# SP26_Magnetometer2_Polarization_Circuit_.net
KiCad netlist of a schematic drawn in Altium Designer
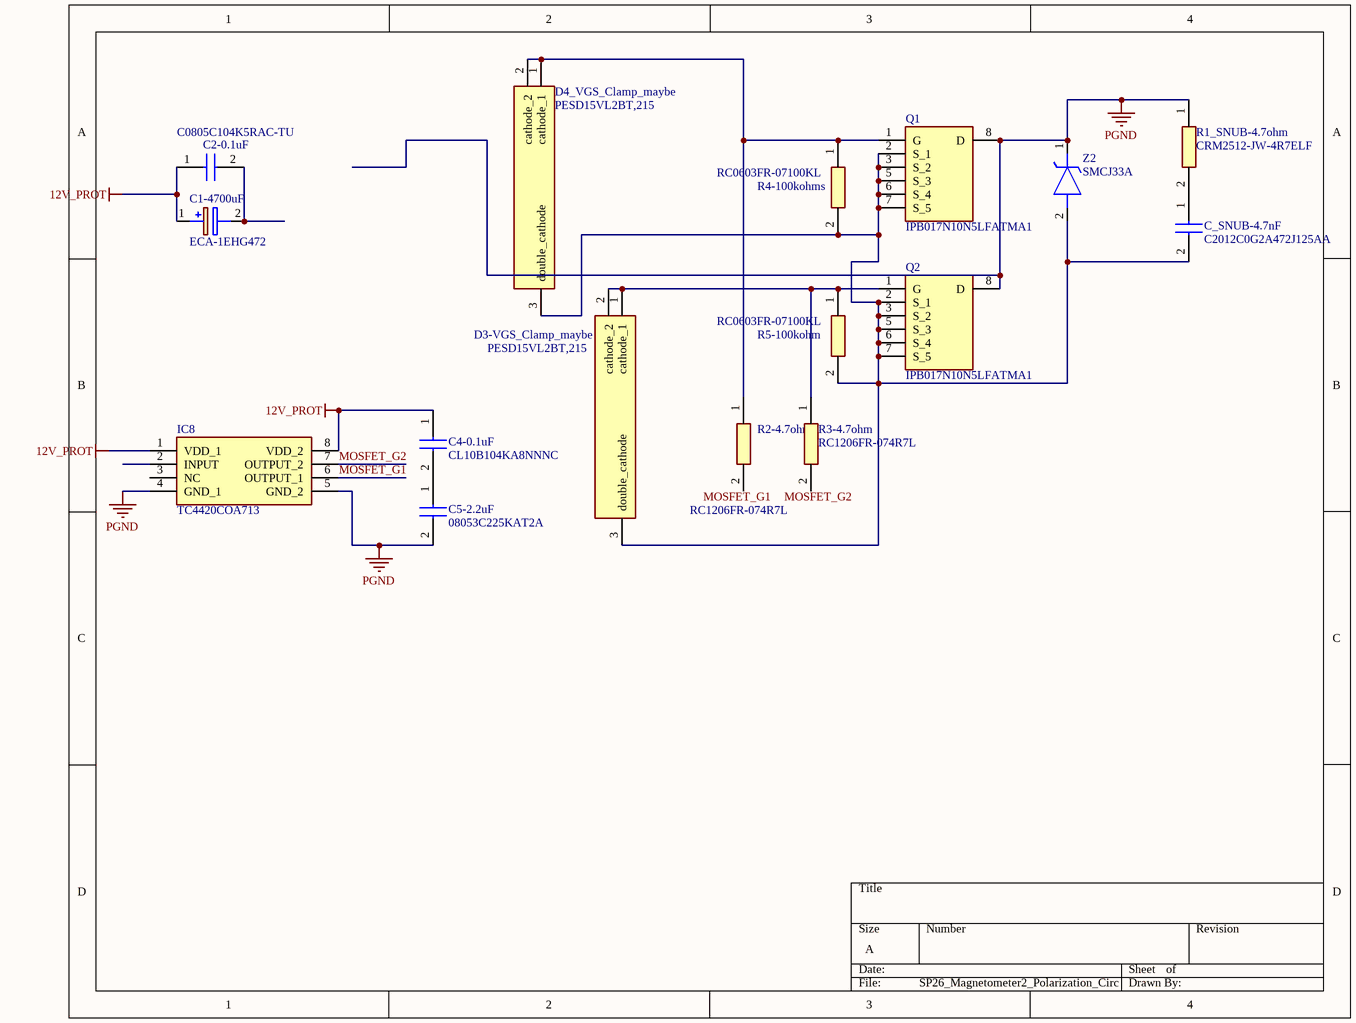
[diagram p0: SP26_Magnetometer2_Polarization_Circuit_Mason_Lebens.SchDoc]

(export (version "E")
  (design (tool "Eeschema 10.0.6"))
  (components
    (comp (ref "C1-4700uF")
      (value "ECA-1EHG472")
      (footprint "SamacSys:CAPPRD750W80D800H3150")
      (description "Capacitor Polarised")
      (fields (field (name "MOUSER PART NUMBER") "667-ECA-1EHG472"))
      (libsource (lib "*") (part "ECA-1EHG472"))
    )
    (comp (ref "C2-0.1uF")
      (value "C0805C104K5RAC-TU")
      (footprint "SamacSys:CAPC2012X88N")
      (description "Capacitor")
      (libsource (lib "*") (part "C0805C104K5RAC-TU"))
    )
    (comp (ref "C4-0.1uF")
      (value "CL10B104KA8NNNC")
      (footprint "SamacSys:CAPC1608X90N")
      (description "Capacitor")
      (fields (field (name "MOUSER PART NUMBER") "187-CL10B104KA8NNNC"))
      (libsource (lib "*") (part "CL10B104KA8NNNC"))
    )
    (comp (ref "C5-2.2uF")
      (value "08053C225KAT2A")
      (footprint "SamacSys:CAPC2012X152N")
      (description "Capacitor")
      (fields (field (name "MOUSER PART NUMBER") "581-08053C225K"))
      (libsource (lib "*") (part "08053C225KAT2A"))
    )
    (comp (ref "C_SNUB-4.7nF")
      (value "C2012C0G2A472J125AA")
      (footprint "SamacSys:CAPC2012X145N")
      (description "Capacitor")
      (fields (field (name "MOUSER PART NUMBER") "810-C2012C0G2A472J"))
      (libsource (lib "*") (part "C2012C0G2A472J125AA"))
    )
    (comp (ref "D3-VGS_Clamp_maybe")
      (value "PESD15VL2BT,215")
      (footprint "SamacSys:SOT95P230X110-3N")
      (description "Diode")
      (fields (field (name "MOUSER PART NUMBER") "771-PESD15VL2BT-T/R"))
      (libsource (lib "*") (part "PESD15VL2BT,215"))
    )
    (comp (ref "D4_VGS_Clamp_maybe")
      (value "PESD15VL2BT,215")
      (footprint "SamacSys:SOT95P230X110-3N")
      (description "Diode")
      (fields (field (name "MOUSER PART NUMBER") "771-PESD15VL2BT-T/R"))
      (libsource (lib "*") (part "PESD15VL2BT,215"))
    )
    (comp (ref "IC8")
      (value "TC4420COA713")
      (footprint "SamacSys:SOIC127P600X175-8N")
      (description "Integrated Circuit")
      (fields (field (name "MOUSER PART NUMBER") "579-TC4420COA713"))
      (libsource (lib "*") (part "TC4420COA713"))
    )
    (comp (ref "Q1")
      (value "IPB017N10N5LFATMA1")
      (footprint "SamacSys:PG-TO263-7-3_3")
      (description "MOSFET (N-Channel)")
      (fields (field (name "MOUSER PART NUMBER") "726-IPB017N10N5LFATM"))
      (libsource (lib "*") (part "IPB017N10N5LFATMA1"))
    )
    (comp (ref "Q2")
      (value "IPB017N10N5LFATMA1")
      (footprint "SamacSys:PG-TO263-7-3_3")
      (description "MOSFET (N-Channel)")
      (fields (field (name "MOUSER PART NUMBER") "726-IPB017N10N5LFATM"))
      (libsource (lib "*") (part "IPB017N10N5LFATMA1"))
    )
    (comp (ref "R1_SNUB-4.7ohm")
      (value "CRM2512-JW-4R7ELF")
      (footprint "SamacSys:RESC6331X80N")
      (description "Resistor")
      (fields (field (name "MOUSER PART NUMBER") "652-CRM2512JW4R7ELF"))
      (libsource (lib "*") (part "CRM2512-JW-4R7ELF"))
    )
    (comp (ref "R2-4.7ohm")
      (value "RC1206FR-074R7L")
      (footprint "SamacSys:RESC3116X65N")
      (description "Resistor")
      (fields (field (name "MOUSER PART NUMBER") "603-RC1206FR-074R7L"))
      (libsource (lib "*") (part "RC1206FR-074R7L"))
    )
    (comp (ref "R3-4.7ohm")
      (value "RC1206FR-074R7L")
      (footprint "SamacSys:RESC3116X65N")
      (description "Resistor")
      (fields (field (name "MOUSER PART NUMBER") "603-RC1206FR-074R7L"))
      (libsource (lib "*") (part "RC1206FR-074R7L"))
    )
    (comp (ref "R4-100kohms")
      (value "RC0603FR-07100KL")
      (footprint "SamacSys:RESC1608X55N")
      (description "Resistor")
      (fields (field (name "MOUSER PART NUMBER") "603-RC0603FR-07100KL"))
      (libsource (lib "*") (part "RC0603FR-07100KL"))
    )
    (comp (ref "R5-100kohm")
      (value "RC0603FR-07100KL")
      (footprint "SamacSys:RESC1608X55N")
      (description "Resistor")
      (fields (field (name "MOUSER PART NUMBER") "603-RC0603FR-07100KL"))
      (libsource (lib "*") (part "RC0603FR-07100KL"))
    )
    (comp (ref "Z2")
      (value "SMCJ33A")
      (footprint "SamacSys:DIOM7969X262N")
      (description "Zener Diode")
      (fields (field (name "MOUSER PART NUMBER") "576-SMCJ33A"))
      (libsource (lib "*") (part "SMCJ33A"))
    )
  )
  (nets
    (net (code "1") (name "/MOSFET_G1") (class "Default")
      (node (ref "IC8") (pin "6") (pinfunction "OUTPUT_1_6") (pintype "passive"))
    )
    (net (code "2") (name "/MOSFET_G2") (class "Default")
      (node (ref "IC8") (pin "7") (pinfunction "OUTPUT_2_7") (pintype "passive"))
    )
    (net (code "3") (name "12V_PROT") (class "Default")
      (node (ref "C1-4700uF") (pin "1") (pinfunction "+_1") (pintype "power_in"))
      (node (ref "C2-0.1uF") (pin "1") (pinfunction "1_1") (pintype "passive"))
      (node (ref "C4-0.1uF") (pin "1") (pinfunction "1_1") (pintype "passive"))
      (node (ref "IC8") (pin "1") (pinfunction "VDD_1_1") (pintype "passive"))
      (node (ref "IC8") (pin "8") (pinfunction "VDD_2_8") (pintype "passive"))
    )
    (net (code "4") (name "Net-(C1-4700uF--)") (class "Default")
      (node (ref "C1-4700uF") (pin "2") (pinfunction "-_2") (pintype "power_in"))
      (node (ref "C2-0.1uF") (pin "2") (pinfunction "2_2") (pintype "passive"))
    )
    (net (code "5") (name "Net-(C4-0.1uF-Pad2)") (class "Default")
      (node (ref "C4-0.1uF") (pin "2") (pinfunction "2_2") (pintype "passive"))
      (node (ref "C5-2.2uF") (pin "1") (pinfunction "1_1") (pintype "passive"))
    )
    (net (code "6") (name "Net-(C_SNUB-4.7nF-Pad1)") (class "Default")
      (node (ref "C_SNUB-4.7nF") (pin "1") (pinfunction "1_1") (pintype "passive"))
      (node (ref "R1_SNUB-4.7ohm") (pin "2") (pinfunction "2_2") (pintype "passive"))
    )
    (net (code "7") (name "Net-(D3-VGS_Clamp_maybe-cathode_1)") (class "Default")
      (node (ref "D3-VGS_Clamp_maybe") (pin "1") (pinfunction "cathode_1_1") (pintype "passive"))
      (node (ref "D3-VGS_Clamp_maybe") (pin "2") (pinfunction "cathode_2_2") (pintype "passive"))
      (node (ref "Q2") (pin "1") (pinfunction "G_1") (pintype "passive"))
      (node (ref "R3-4.7ohm") (pin "1") (pinfunction "1_1") (pintype "passive"))
      (node (ref "R5-100kohm") (pin "1") (pinfunction "1_1") (pintype "passive"))
    )
    (net (code "8") (name "Net-(D3-VGS_Clamp_maybe-double_cathode)") (class "Default")
      (node (ref "C_SNUB-4.7nF") (pin "2") (pinfunction "2_2") (pintype "passive"))
      (node (ref "D3-VGS_Clamp_maybe") (pin "3") (pinfunction "double_cathode_3") (pintype "passive"))
      (node (ref "D4_VGS_Clamp_maybe") (pin "3") (pinfunction "double_cathode_3") (pintype "passive"))
      (node (ref "Q1") (pin "2") (pinfunction "S_1_2") (pintype "passive"))
      (node (ref "Q1") (pin "3") (pinfunction "S_2_3") (pintype "passive"))
      (node (ref "Q1") (pin "5") (pinfunction "S_3_5") (pintype "passive"))
      (node (ref "Q1") (pin "6") (pinfunction "S_4_6") (pintype "passive"))
      (node (ref "Q1") (pin "7") (pinfunction "S_5_7") (pintype "passive"))
      (node (ref "Q2") (pin "2") (pinfunction "S_1_2") (pintype "passive"))
      (node (ref "Q2") (pin "3") (pinfunction "S_2_3") (pintype "passive"))
      (node (ref "Q2") (pin "5") (pinfunction "S_3_5") (pintype "passive"))
      (node (ref "Q2") (pin "6") (pinfunction "S_4_6") (pintype "passive"))
      (node (ref "Q2") (pin "7") (pinfunction "S_5_7") (pintype "passive"))
      (node (ref "R4-100kohms") (pin "2") (pinfunction "2_2") (pintype "passive"))
      (node (ref "R5-100kohm") (pin "2") (pinfunction "2_2") (pintype "passive"))
      (node (ref "Z2") (pin "2") (pinfunction "A_2") (pintype "passive"))
    )
    (net (code "9") (name "Net-(D4_VGS_Clamp_maybe-cathode_1)") (class "Default")
      (node (ref "D4_VGS_Clamp_maybe") (pin "1") (pinfunction "cathode_1_1") (pintype "passive"))
      (node (ref "D4_VGS_Clamp_maybe") (pin "2") (pinfunction "cathode_2_2") (pintype "passive"))
      (node (ref "Q1") (pin "1") (pinfunction "G_1") (pintype "passive"))
      (node (ref "R2-4.7ohm") (pin "1") (pinfunction "1_1") (pintype "passive"))
      (node (ref "R4-100kohms") (pin "1") (pinfunction "1_1") (pintype "passive"))
    )
    (net (code "10") (name "PGND") (class "Default")
      (node (ref "C5-2.2uF") (pin "2") (pinfunction "2_2") (pintype "passive"))
      (node (ref "IC8") (pin "4") (pinfunction "GND_1_4") (pintype "passive"))
      (node (ref "IC8") (pin "5") (pinfunction "GND_2_5") (pintype "passive"))
      (node (ref "Q1") (pin "8") (pinfunction "D_8") (pintype "passive"))
      (node (ref "Q2") (pin "8") (pinfunction "D_8") (pintype "passive"))
      (node (ref "R1_SNUB-4.7ohm") (pin "1") (pinfunction "1_1") (pintype "passive"))
      (node (ref "Z2") (pin "1") (pinfunction "K_1") (pintype "passive"))
    )
    (net (code "11") (name "unconnected-(IC8-INPUT-Pad2)") (class "Default")
      (node (ref "IC8") (pin "2") (pinfunction "INPUT_2") (pintype "passive"))
    )
    (net (code "12") (name "unconnected-(IC8-NC-Pad3)") (class "Default")
      (node (ref "IC8") (pin "3") (pinfunction "NC_3") (pintype "passive"))
    )
    (net (code "13") (name "unconnected-(R2-4.7ohm-Pad2)") (class "Default")
      (node (ref "R2-4.7ohm") (pin "2") (pinfunction "2_2") (pintype "passive"))
    )
    (net (code "14") (name "unconnected-(R3-4.7ohm-Pad2)") (class "Default")
      (node (ref "R3-4.7ohm") (pin "2") (pinfunction "2_2") (pintype "passive"))
    )
  )
)
